# 00-INDEX.net
KiCad netlist of a schematic drawn in Altium Designer
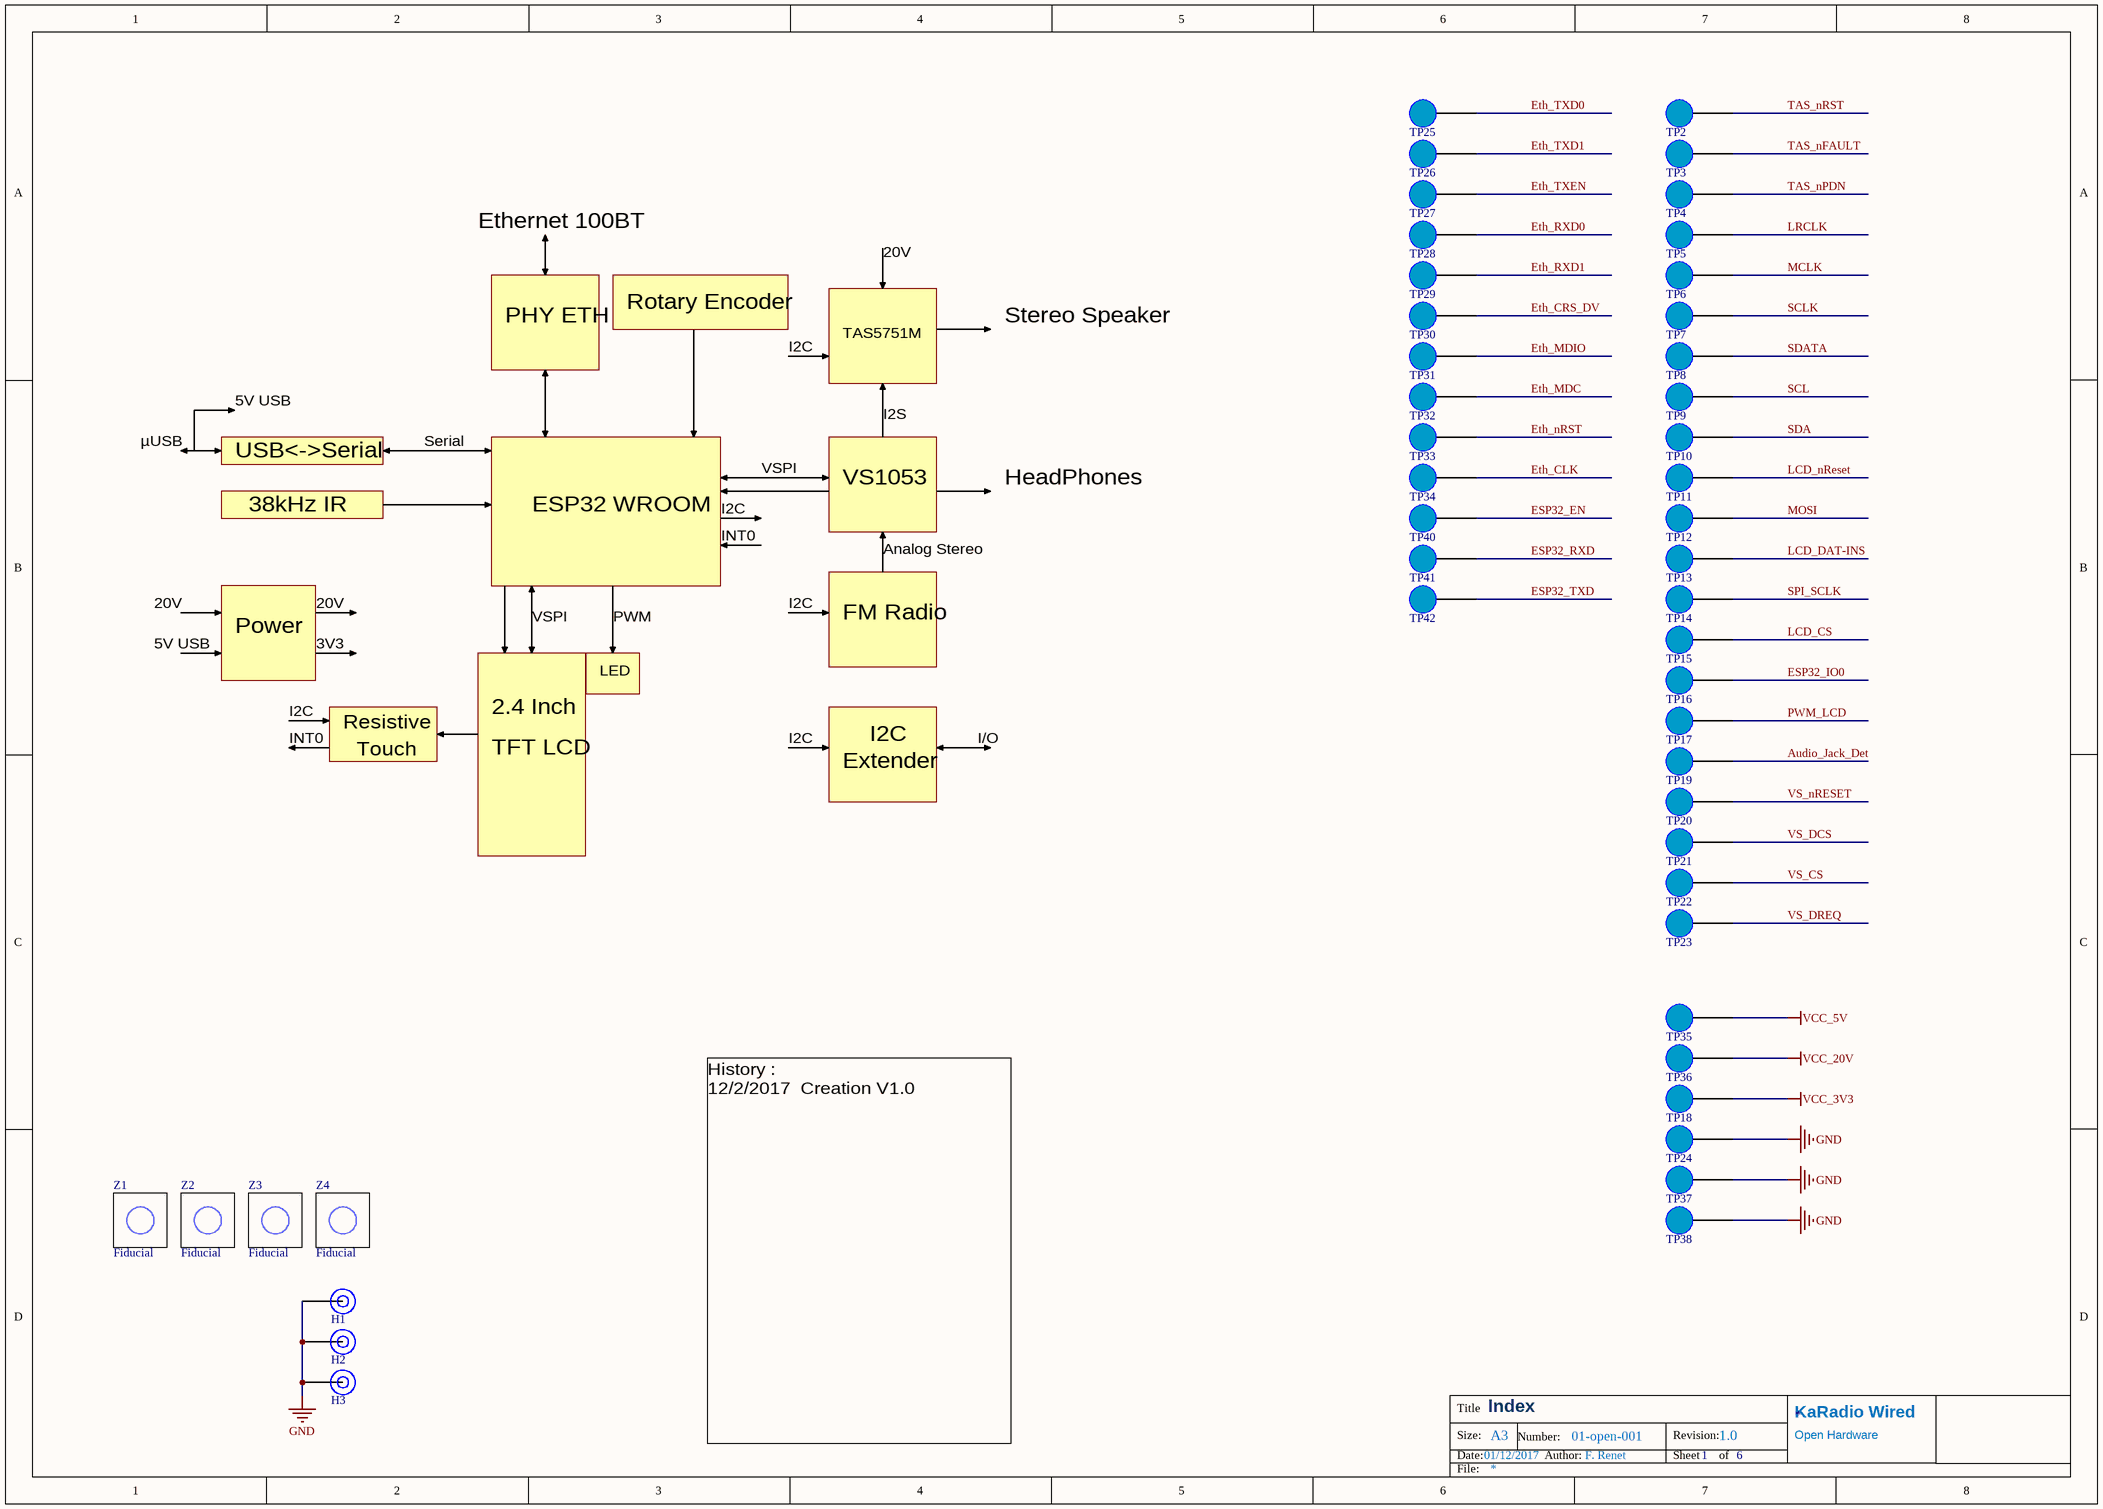
[diagram p0: 00-INDEX.SchDoc]

(export (version "E")
  (design (tool "Eeschema 10.0.6"))
  (components
    (comp (ref "H1")
      (value "Hole_Screw_3mm")
      (footprint "Aptustech:Hole_3.2mm")
      (description "Fix hole 3mm screw")
      (libsource (lib "Mech") (part "Hole_Screw_3mm"))
    )
    (comp (ref "H2")
      (value "Hole_Screw_3mm")
      (footprint "Aptustech:Hole_3.2mm")
      (description "Fix hole 3mm screw")
      (libsource (lib "Mech") (part "Hole_Screw_3mm"))
    )
    (comp (ref "H3")
      (value "Hole_Screw_3mm")
      (footprint "Aptustech:Hole_3.2mm")
      (description "Fix hole 3mm screw")
      (libsource (lib "Mech") (part "Hole_Screw_3mm"))
    )
    (comp (ref "TP2")
      (value "TP_1mm")
      (footprint "Aptustech:TP_1mm")
      (description "Test point 1mm round SMD")
      (libsource (lib "Mech") (part "TP_1mm"))
    )
    (comp (ref "TP3")
      (value "TP_1mm")
      (footprint "Aptustech:TP_1mm")
      (description "Test point 1mm round SMD")
      (libsource (lib "Mech") (part "TP_1mm"))
    )
    (comp (ref "TP4")
      (value "TP_1mm")
      (footprint "Aptustech:TP_1mm")
      (description "Test point 1mm round SMD")
      (libsource (lib "Mech") (part "TP_1mm"))
    )
    (comp (ref "TP5")
      (value "TP_1mm")
      (footprint "Aptustech:TP_1mm")
      (description "Test point 1mm round SMD")
      (libsource (lib "Mech") (part "TP_1mm"))
    )
    (comp (ref "TP6")
      (value "TP_1mm")
      (footprint "Aptustech:TP_1mm")
      (description "Test point 1mm round SMD")
      (libsource (lib "Mech") (part "TP_1mm"))
    )
    (comp (ref "TP7")
      (value "TP_1mm")
      (footprint "Aptustech:TP_1mm")
      (description "Test point 1mm round SMD")
      (libsource (lib "Mech") (part "TP_1mm"))
    )
    (comp (ref "TP8")
      (value "TP_1mm")
      (footprint "Aptustech:TP_1mm")
      (description "Test point 1mm round SMD")
      (libsource (lib "Mech") (part "TP_1mm"))
    )
    (comp (ref "TP9")
      (value "TP_1mm")
      (footprint "Aptustech:TP_1mm")
      (description "Test point 1mm round SMD")
      (libsource (lib "Mech") (part "TP_1mm"))
    )
    (comp (ref "TP10")
      (value "TP_1mm")
      (footprint "Aptustech:TP_1mm")
      (description "Test point 1mm round SMD")
      (libsource (lib "Mech") (part "TP_1mm"))
    )
    (comp (ref "TP11")
      (value "TP_1mm")
      (footprint "Aptustech:TP_1mm")
      (description "Test point 1mm round SMD")
      (libsource (lib "Mech") (part "TP_1mm"))
    )
    (comp (ref "TP12")
      (value "TP_1mm")
      (footprint "Aptustech:TP_1mm")
      (description "Test point 1mm round SMD")
      (libsource (lib "Mech") (part "TP_1mm"))
    )
    (comp (ref "TP13")
      (value "TP_1mm")
      (footprint "Aptustech:TP_1mm")
      (description "Test point 1mm round SMD")
      (libsource (lib "Mech") (part "TP_1mm"))
    )
    (comp (ref "TP14")
      (value "TP_1mm")
      (footprint "Aptustech:TP_1mm")
      (description "Test point 1mm round SMD")
      (libsource (lib "Mech") (part "TP_1mm"))
    )
    (comp (ref "TP15")
      (value "TP_1mm")
      (footprint "Aptustech:TP_1mm")
      (description "Test point 1mm round SMD")
      (libsource (lib "Mech") (part "TP_1mm"))
    )
    (comp (ref "TP16")
      (value "TP_1mm")
      (footprint "Aptustech:TP_1mm")
      (description "Test point 1mm round SMD")
      (libsource (lib "Mech") (part "TP_1mm"))
    )
    (comp (ref "TP17")
      (value "TP_1mm")
      (footprint "Aptustech:TP_1mm")
      (description "Test point 1mm round SMD")
      (libsource (lib "Mech") (part "TP_1mm"))
    )
    (comp (ref "TP18")
      (value "TP_1mm")
      (footprint "Aptustech:TP_1mm")
      (description "Test point 1mm round SMD")
      (libsource (lib "Mech") (part "TP_1mm"))
    )
    (comp (ref "TP19")
      (value "TP_1mm")
      (footprint "Aptustech:TP_1mm")
      (description "Test point 1mm round SMD")
      (libsource (lib "Mech") (part "TP_1mm"))
    )
    (comp (ref "TP20")
      (value "TP_1mm")
      (footprint "Aptustech:TP_1mm")
      (description "Test point 1mm round SMD")
      (libsource (lib "Mech") (part "TP_1mm"))
    )
    (comp (ref "TP21")
      (value "TP_1mm")
      (footprint "Aptustech:TP_1mm")
      (description "Test point 1mm round SMD")
      (libsource (lib "Mech") (part "TP_1mm"))
    )
    (comp (ref "TP22")
      (value "TP_1mm")
      (footprint "Aptustech:TP_1mm")
      (description "Test point 1mm round SMD")
      (libsource (lib "Mech") (part "TP_1mm"))
    )
    (comp (ref "TP23")
      (value "TP_1mm")
      (footprint "Aptustech:TP_1mm")
      (description "Test point 1mm round SMD")
      (libsource (lib "Mech") (part "TP_1mm"))
    )
    (comp (ref "TP24")
      (value "TP_1mm")
      (footprint "Aptustech:TP_1mm")
      (description "Test point 1mm round SMD")
      (libsource (lib "Mech") (part "TP_1mm"))
    )
    (comp (ref "TP25")
      (value "TP_1mm")
      (footprint "Aptustech:TP_1mm")
      (description "Test point 1mm round SMD")
      (libsource (lib "Mech") (part "TP_1mm"))
    )
    (comp (ref "TP26")
      (value "TP_1mm")
      (footprint "Aptustech:TP_1mm")
      (description "Test point 1mm round SMD")
      (libsource (lib "Mech") (part "TP_1mm"))
    )
    (comp (ref "TP27")
      (value "TP_1mm")
      (footprint "Aptustech:TP_1mm")
      (description "Test point 1mm round SMD")
      (libsource (lib "Mech") (part "TP_1mm"))
    )
    (comp (ref "TP28")
      (value "TP_1mm")
      (footprint "Aptustech:TP_1mm")
      (description "Test point 1mm round SMD")
      (libsource (lib "Mech") (part "TP_1mm"))
    )
    (comp (ref "TP29")
      (value "TP_1mm")
      (footprint "Aptustech:TP_1mm")
      (description "Test point 1mm round SMD")
      (libsource (lib "Mech") (part "TP_1mm"))
    )
    (comp (ref "TP30")
      (value "TP_1mm")
      (footprint "Aptustech:TP_1mm")
      (description "Test point 1mm round SMD")
      (libsource (lib "Mech") (part "TP_1mm"))
    )
    (comp (ref "TP31")
      (value "TP_1mm")
      (footprint "Aptustech:TP_1mm")
      (description "Test point 1mm round SMD")
      (libsource (lib "Mech") (part "TP_1mm"))
    )
    (comp (ref "TP32")
      (value "TP_1mm")
      (footprint "Aptustech:TP_1mm")
      (description "Test point 1mm round SMD")
      (libsource (lib "Mech") (part "TP_1mm"))
    )
    (comp (ref "TP33")
      (value "TP_1mm")
      (footprint "Aptustech:TP_1mm")
      (description "Test point 1mm round SMD")
      (libsource (lib "Mech") (part "TP_1mm"))
    )
    (comp (ref "TP34")
      (value "TP_1mm")
      (footprint "Aptustech:TP_1mm")
      (description "Test point 1mm round SMD")
      (libsource (lib "Mech") (part "TP_1mm"))
    )
    (comp (ref "TP35")
      (value "TP_1mm")
      (footprint "Aptustech:TP_1mm")
      (description "Test point 1mm round SMD")
      (libsource (lib "Mech") (part "TP_1mm"))
    )
    (comp (ref "TP36")
      (value "TP_1mm")
      (footprint "Aptustech:TP_1mm")
      (description "Test point 1mm round SMD")
      (libsource (lib "Mech") (part "TP_1mm"))
    )
    (comp (ref "TP37")
      (value "TP_1mm")
      (footprint "Aptustech:TP_1mm")
      (description "Test point 1mm round SMD")
      (libsource (lib "Mech") (part "TP_1mm"))
    )
    (comp (ref "TP38")
      (value "TP_1mm")
      (footprint "Aptustech:TP_1mm")
      (description "Test point 1mm round SMD")
      (libsource (lib "Mech") (part "TP_1mm"))
    )
    (comp (ref "TP40")
      (value "TP_1mm")
      (footprint "Aptustech:TP_1mm")
      (description "Test point 1mm round SMD")
      (libsource (lib "Mech") (part "TP_1mm"))
    )
    (comp (ref "TP41")
      (value "TP_1mm")
      (footprint "Aptustech:TP_1mm")
      (description "Test point 1mm round SMD")
      (libsource (lib "Mech") (part "TP_1mm"))
    )
    (comp (ref "TP42")
      (value "TP_1mm")
      (footprint "Aptustech:TP_1mm")
      (description "Test point 1mm round SMD")
      (libsource (lib "Mech") (part "TP_1mm"))
    )
    (comp (ref "Z1")
      (value "Fiducial")
      (footprint "Aptustech:Fiducial_1mm")
      (description "1mm Fiducial")
      (libsource (lib "Mech") (part "Fiducial"))
    )
    (comp (ref "Z2")
      (value "Fiducial")
      (footprint "Aptustech:Fiducial_1mm")
      (description "1mm Fiducial")
      (libsource (lib "Mech") (part "Fiducial"))
    )
    (comp (ref "Z3")
      (value "Fiducial")
      (footprint "Aptustech:Fiducial_1mm")
      (description "1mm Fiducial")
      (libsource (lib "Mech") (part "Fiducial"))
    )
    (comp (ref "Z4")
      (value "Fiducial")
      (footprint "Aptustech:Fiducial_1mm")
      (description "1mm Fiducial")
      (libsource (lib "Mech") (part "Fiducial"))
    )
  )
  (nets
    (net (code "1") (name "/Audio_Jack_Det") (class "Default")
      (node (ref "TP19") (pin "1") (pinfunction "1_1") (pintype "passive"))
    )
    (net (code "2") (name "/ESP32_EN") (class "Default")
      (node (ref "TP40") (pin "1") (pinfunction "1_1") (pintype "passive"))
    )
    (net (code "3") (name "/ESP32_IO0") (class "Default")
      (node (ref "TP16") (pin "1") (pinfunction "1_1") (pintype "passive"))
    )
    (net (code "4") (name "/ESP32_RXD") (class "Default")
      (node (ref "TP41") (pin "1") (pinfunction "1_1") (pintype "passive"))
    )
    (net (code "5") (name "/ESP32_TXD") (class "Default")
      (node (ref "TP42") (pin "1") (pinfunction "1_1") (pintype "passive"))
    )
    (net (code "6") (name "/Eth_CLK") (class "Default")
      (node (ref "TP34") (pin "1") (pinfunction "1_1") (pintype "passive"))
    )
    (net (code "7") (name "/Eth_CRS_DV") (class "Default")
      (node (ref "TP30") (pin "1") (pinfunction "1_1") (pintype "passive"))
    )
    (net (code "8") (name "/Eth_MDC") (class "Default")
      (node (ref "TP32") (pin "1") (pinfunction "1_1") (pintype "passive"))
    )
    (net (code "9") (name "/Eth_MDIO") (class "Default")
      (node (ref "TP31") (pin "1") (pinfunction "1_1") (pintype "passive"))
    )
    (net (code "10") (name "/Eth_RXD0") (class "Default")
      (node (ref "TP28") (pin "1") (pinfunction "1_1") (pintype "passive"))
    )
    (net (code "11") (name "/Eth_RXD1") (class "Default")
      (node (ref "TP29") (pin "1") (pinfunction "1_1") (pintype "passive"))
    )
    (net (code "12") (name "/Eth_TXD0") (class "Default")
      (node (ref "TP25") (pin "1") (pinfunction "1_1") (pintype "passive"))
    )
    (net (code "13") (name "/Eth_TXD1") (class "Default")
      (node (ref "TP26") (pin "1") (pinfunction "1_1") (pintype "passive"))
    )
    (net (code "14") (name "/Eth_TXEN") (class "Default")
      (node (ref "TP27") (pin "1") (pinfunction "1_1") (pintype "passive"))
    )
    (net (code "15") (name "/Eth_nRST") (class "Default")
      (node (ref "TP33") (pin "1") (pinfunction "1_1") (pintype "passive"))
    )
    (net (code "16") (name "/LCD_CS") (class "Default")
      (node (ref "TP15") (pin "1") (pinfunction "1_1") (pintype "passive"))
    )
    (net (code "17") (name "/LCD_DAT-INS") (class "Default")
      (node (ref "TP13") (pin "1") (pinfunction "1_1") (pintype "passive"))
    )
    (net (code "18") (name "/LCD_nReset") (class "Default")
      (node (ref "TP11") (pin "1") (pinfunction "1_1") (pintype "passive"))
    )
    (net (code "19") (name "/LRCLK") (class "Default")
      (node (ref "TP5") (pin "1") (pinfunction "1_1") (pintype "passive"))
    )
    (net (code "20") (name "/MCLK") (class "Default")
      (node (ref "TP6") (pin "1") (pinfunction "1_1") (pintype "passive"))
    )
    (net (code "21") (name "/MOSI") (class "Default")
      (node (ref "TP12") (pin "1") (pinfunction "1_1") (pintype "passive"))
    )
    (net (code "22") (name "/PWM_LCD") (class "Default")
      (node (ref "TP17") (pin "1") (pinfunction "1_1") (pintype "passive"))
    )
    (net (code "23") (name "/SCL") (class "Default")
      (node (ref "TP9") (pin "1") (pinfunction "1_1") (pintype "passive"))
    )
    (net (code "24") (name "/SCLK") (class "Default")
      (node (ref "TP7") (pin "1") (pinfunction "1_1") (pintype "passive"))
    )
    (net (code "25") (name "/SDA") (class "Default")
      (node (ref "TP10") (pin "1") (pinfunction "1_1") (pintype "passive"))
    )
    (net (code "26") (name "/SDATA") (class "Default")
      (node (ref "TP8") (pin "1") (pinfunction "1_1") (pintype "passive"))
    )
    (net (code "27") (name "/SPI_SCLK") (class "Default")
      (node (ref "TP14") (pin "1") (pinfunction "1_1") (pintype "passive"))
    )
    (net (code "28") (name "/TAS_nFAULT") (class "Default")
      (node (ref "TP3") (pin "1") (pinfunction "1_1") (pintype "passive"))
    )
    (net (code "29") (name "/TAS_nPDN") (class "Default")
      (node (ref "TP4") (pin "1") (pinfunction "1_1") (pintype "passive"))
    )
    (net (code "30") (name "/TAS_nRST") (class "Default")
      (node (ref "TP2") (pin "1") (pinfunction "1_1") (pintype "passive"))
    )
    (net (code "31") (name "/VS_CS") (class "Default")
      (node (ref "TP22") (pin "1") (pinfunction "1_1") (pintype "passive"))
    )
    (net (code "32") (name "/VS_DCS") (class "Default")
      (node (ref "TP21") (pin "1") (pinfunction "1_1") (pintype "passive"))
    )
    (net (code "33") (name "/VS_DREQ") (class "Default")
      (node (ref "TP23") (pin "1") (pinfunction "1_1") (pintype "passive"))
    )
    (net (code "34") (name "/VS_nRESET") (class "Default")
      (node (ref "TP20") (pin "1") (pinfunction "1_1") (pintype "passive"))
    )
    (net (code "35") (name "GND") (class "Default")
      (node (ref "H1") (pin "1") (pinfunction "1_1") (pintype "passive"))
      (node (ref "H2") (pin "1") (pinfunction "1_1") (pintype "passive"))
      (node (ref "H3") (pin "1") (pinfunction "1_1") (pintype "passive"))
      (node (ref "TP24") (pin "1") (pinfunction "1_1") (pintype "passive"))
      (node (ref "TP37") (pin "1") (pinfunction "1_1") (pintype "passive"))
      (node (ref "TP38") (pin "1") (pinfunction "1_1") (pintype "passive"))
    )
    (net (code "36") (name "VCC_3V3") (class "Default")
      (node (ref "TP18") (pin "1") (pinfunction "1_1") (pintype "passive"))
    )
    (net (code "37") (name "VCC_5V") (class "Default")
      (node (ref "TP35") (pin "1") (pinfunction "1_1") (pintype "passive"))
    )
    (net (code "38") (name "VCC_20V") (class "Default")
      (node (ref "TP36") (pin "1") (pinfunction "1_1") (pintype "passive"))
    )
  )
)
